# switch-QPC1022_v2.net
KiCad netlist of a schematic drawn in EAGLE
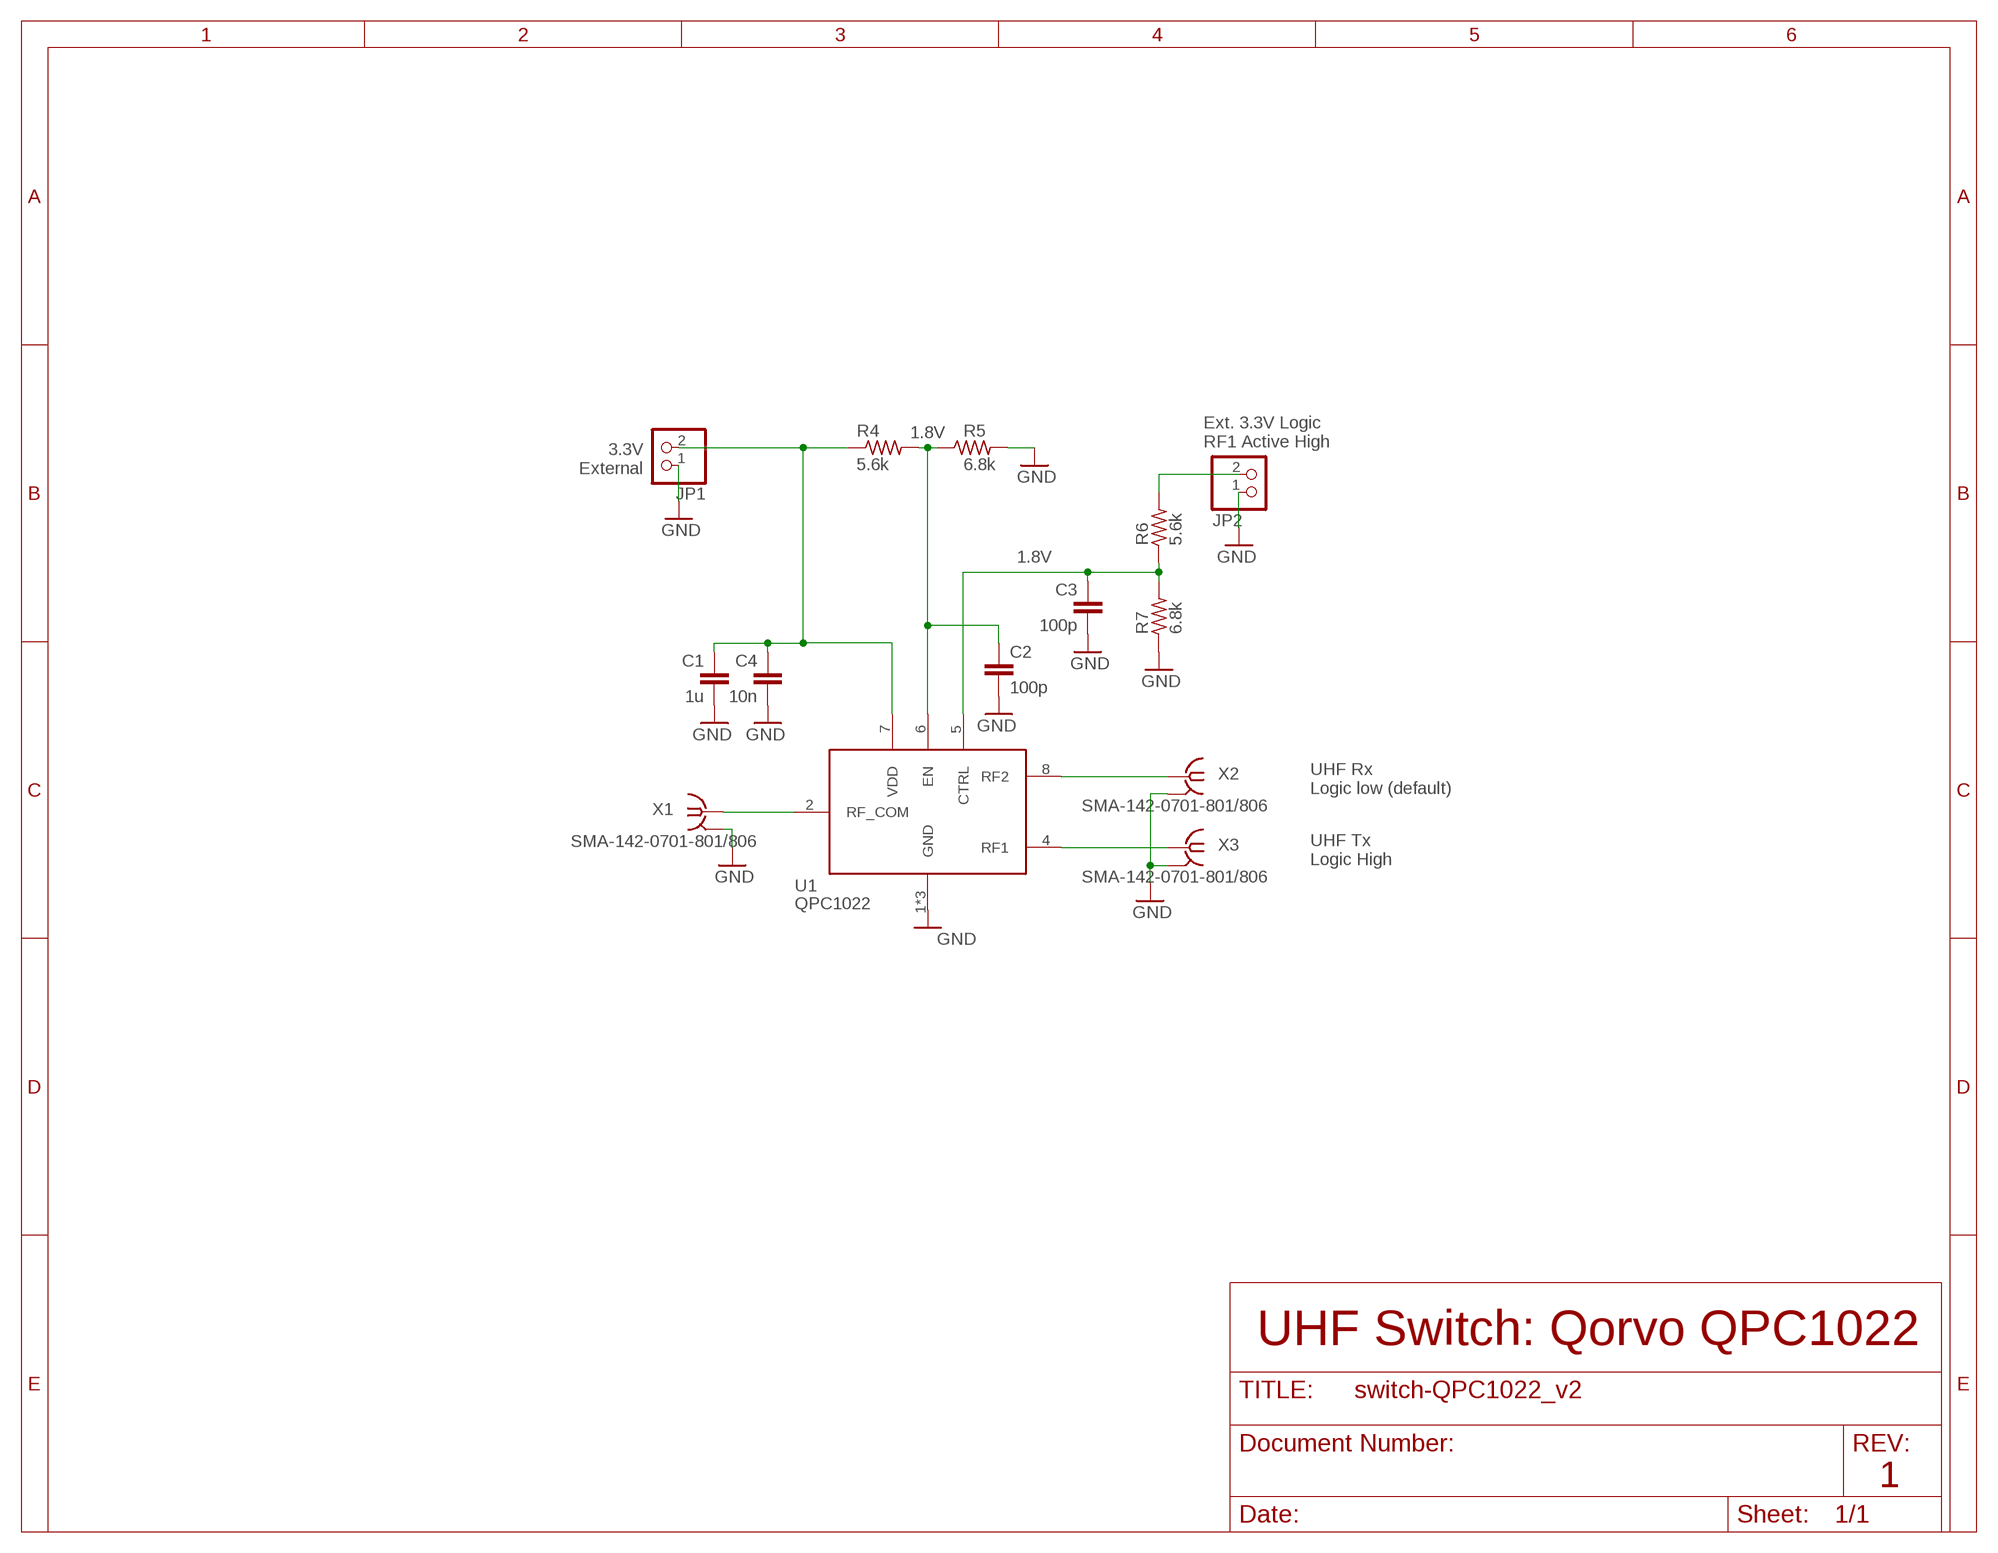
[diagram p0: schematic, sheet 1]

(export (version "E")
  (design (tool "Eeschema 10.0.6"))
  (components
    (comp (ref "C1")
      (value "1u")
      (footprint "eagle-import:.0603-B-NOSILK")
      (libsource (lib "eagle-import") (part "C-EU0603-B-NOSILK"))
    )
    (comp (ref "C2")
      (value "100p")
      (footprint "eagle-import:.0402-B-NOSILK")
      (libsource (lib "eagle-import") (part "C-EU0402-B-NOSILK"))
    )
    (comp (ref "C3")
      (value "100p")
      (footprint "eagle-import:.0402-B-NOSILK")
      (libsource (lib "eagle-import") (part "C-EU0402-B-NOSILK"))
    )
    (comp (ref "C4")
      (value "10n")
      (footprint "eagle-import:.0603-B-NOSILK")
      (libsource (lib "eagle-import") (part "C-EU0603-B-NOSILK"))
    )
    (comp (ref "JP1")
      (value "PINHD-1X2")
      (footprint "eagle-import:1X02")
      (libsource (lib "eagle-import") (part "PINHD-1X2"))
    )
    (comp (ref "JP2")
      (value "PINHD-1X2")
      (footprint "eagle-import:1X02")
      (libsource (lib "eagle-import") (part "PINHD-1X2"))
    )
    (comp (ref "R4")
      (value "5.6k")
      (footprint "eagle-import:.0402-B-NOSILK")
      (libsource (lib "eagle-import") (part "R-US_0402-B-NOSILK"))
    )
    (comp (ref "R5")
      (value "6.8k")
      (footprint "eagle-import:.0402-B-NOSILK")
      (libsource (lib "eagle-import") (part "R-US_0402-B-NOSILK"))
    )
    (comp (ref "R6")
      (value "5.6k")
      (footprint "eagle-import:.0402-B-NOSILK")
      (libsource (lib "eagle-import") (part "R-US_0402-B-NOSILK"))
    )
    (comp (ref "R7")
      (value "6.8k")
      (footprint "eagle-import:.0402-B-NOSILK")
      (libsource (lib "eagle-import") (part "R-US_0402-B-NOSILK"))
    )
    (comp (ref "U1")
      (value "QPC1022")
      (footprint "eagle-import:QPC1022")
      (fields (field (name "MFR") "Qorvo"))
      (libsource (lib "eagle-import") (part "QPC1022"))
    )
    (comp (ref "X1")
      (value "SMA-142-0701-801/806")
      (footprint "eagle-import:J502-ND-142-0701-801_806")
      (fields (field (name "MF") "JOHNSON COMPONENTS") (field (name "MPN") "142-0701-801"))
      (libsource (lib "eagle-import") (part "SMA-142-0701-801/806"))
    )
    (comp (ref "X2")
      (value "SMA-142-0701-801/806")
      (footprint "eagle-import:J502-ND-142-0701-801_806")
      (fields (field (name "MF") "JOHNSON COMPONENTS") (field (name "MPN") "142-0701-801"))
      (libsource (lib "eagle-import") (part "SMA-142-0701-801/806"))
    )
    (comp (ref "X3")
      (value "SMA-142-0701-801/806")
      (footprint "eagle-import:J502-ND-142-0701-801_806")
      (fields (field (name "MF") "JOHNSON COMPONENTS") (field (name "MPN") "142-0701-801"))
      (libsource (lib "eagle-import") (part "SMA-142-0701-801/806"))
    )
  )
  (nets
    (net (code "1") (name "GND") (class "Default")
      (node (ref "C1") (pin "2") (pinfunction "2_2") (pintype "passive"))
      (node (ref "C2") (pin "2") (pinfunction "2_2") (pintype "passive"))
      (node (ref "C3") (pin "2") (pinfunction "2_2") (pintype "passive"))
      (node (ref "C4") (pin "2") (pinfunction "2_2") (pintype "passive"))
      (node (ref "JP1") (pin "1") (pinfunction "1_1") (pintype "passive"))
      (node (ref "JP2") (pin "1") (pinfunction "1_1") (pintype "passive"))
      (node (ref "R5") (pin "2") (pinfunction "2_2") (pintype "passive"))
      (node (ref "R7") (pin "1") (pinfunction "1_1") (pintype "passive"))
      (node (ref "U1") (pin "1") (pinfunction "GND_1") (pintype "power_in"))
      (node (ref "U1") (pin "3") (pinfunction "GND_3") (pintype "power_in"))
      (node (ref "U1") (pin "9") (pinfunction "GND_9") (pintype "power_in"))
      (node (ref "X1") (pin "G@1") (pinfunction "2_G@1") (pintype "passive"))
      (node (ref "X1") (pin "G@2") (pinfunction "2_G@2") (pintype "passive"))
      (node (ref "X1") (pin "G@3") (pinfunction "2_G@3") (pintype "passive"))
      (node (ref "X1") (pin "G@4") (pinfunction "2_G@4") (pintype "passive"))
      (node (ref "X2") (pin "G@1") (pinfunction "2_G@1") (pintype "passive"))
      (node (ref "X2") (pin "G@2") (pinfunction "2_G@2") (pintype "passive"))
      (node (ref "X2") (pin "G@3") (pinfunction "2_G@3") (pintype "passive"))
      (node (ref "X2") (pin "G@4") (pinfunction "2_G@4") (pintype "passive"))
      (node (ref "X3") (pin "G@1") (pinfunction "2_G@1") (pintype "passive"))
      (node (ref "X3") (pin "G@2") (pinfunction "2_G@2") (pintype "passive"))
      (node (ref "X3") (pin "G@3") (pinfunction "2_G@3") (pintype "passive"))
      (node (ref "X3") (pin "G@4") (pinfunction "2_G@4") (pintype "passive"))
    )
    (net (code "2") (name "Net-(JP2-Pad2)") (class "Default")
      (node (ref "JP2") (pin "2") (pinfunction "2_2") (pintype "passive"))
      (node (ref "R6") (pin "2") (pinfunction "2_2") (pintype "passive"))
    )
    (net (code "3") (name "Net-(U1-CTRL)") (class "Default")
      (node (ref "C3") (pin "1") (pinfunction "1_1") (pintype "passive"))
      (node (ref "R6") (pin "1") (pinfunction "1_1") (pintype "passive"))
      (node (ref "R7") (pin "2") (pinfunction "2_2") (pintype "passive"))
      (node (ref "U1") (pin "5") (pinfunction "CTRL_5") (pintype "bidirectional"))
    )
    (net (code "4") (name "Net-(U1-EN)") (class "Default")
      (node (ref "C2") (pin "1") (pinfunction "1_1") (pintype "passive"))
      (node (ref "R4") (pin "2") (pinfunction "2_2") (pintype "passive"))
      (node (ref "R5") (pin "1") (pinfunction "1_1") (pintype "passive"))
      (node (ref "U1") (pin "6") (pinfunction "EN_6") (pintype "bidirectional"))
    )
    (net (code "5") (name "Net-(U1-RF1)") (class "Default")
      (node (ref "U1") (pin "4") (pinfunction "RF1_4") (pintype "bidirectional"))
      (node (ref "X3") (pin "1") (pinfunction "1_1") (pintype "passive"))
    )
    (net (code "6") (name "Net-(U1-RF2)") (class "Default")
      (node (ref "U1") (pin "8") (pinfunction "RF2_8") (pintype "bidirectional"))
      (node (ref "X2") (pin "1") (pinfunction "1_1") (pintype "passive"))
    )
    (net (code "7") (name "Net-(U1-RF_COM)") (class "Default")
      (node (ref "U1") (pin "2") (pinfunction "RF_COM_2") (pintype "bidirectional"))
      (node (ref "X1") (pin "1") (pinfunction "1_1") (pintype "passive"))
    )
    (net (code "8") (name "Net-(U1-VDD)") (class "Default")
      (node (ref "C1") (pin "1") (pinfunction "1_1") (pintype "passive"))
      (node (ref "C4") (pin "1") (pinfunction "1_1") (pintype "passive"))
      (node (ref "JP1") (pin "2") (pinfunction "2_2") (pintype "passive"))
      (node (ref "R4") (pin "1") (pinfunction "1_1") (pintype "passive"))
      (node (ref "U1") (pin "7") (pinfunction "VDD_7") (pintype "power_in"))
    )
  )
)
